# FPGA.net
KiCad netlist of a schematic drawn in Altium Designer
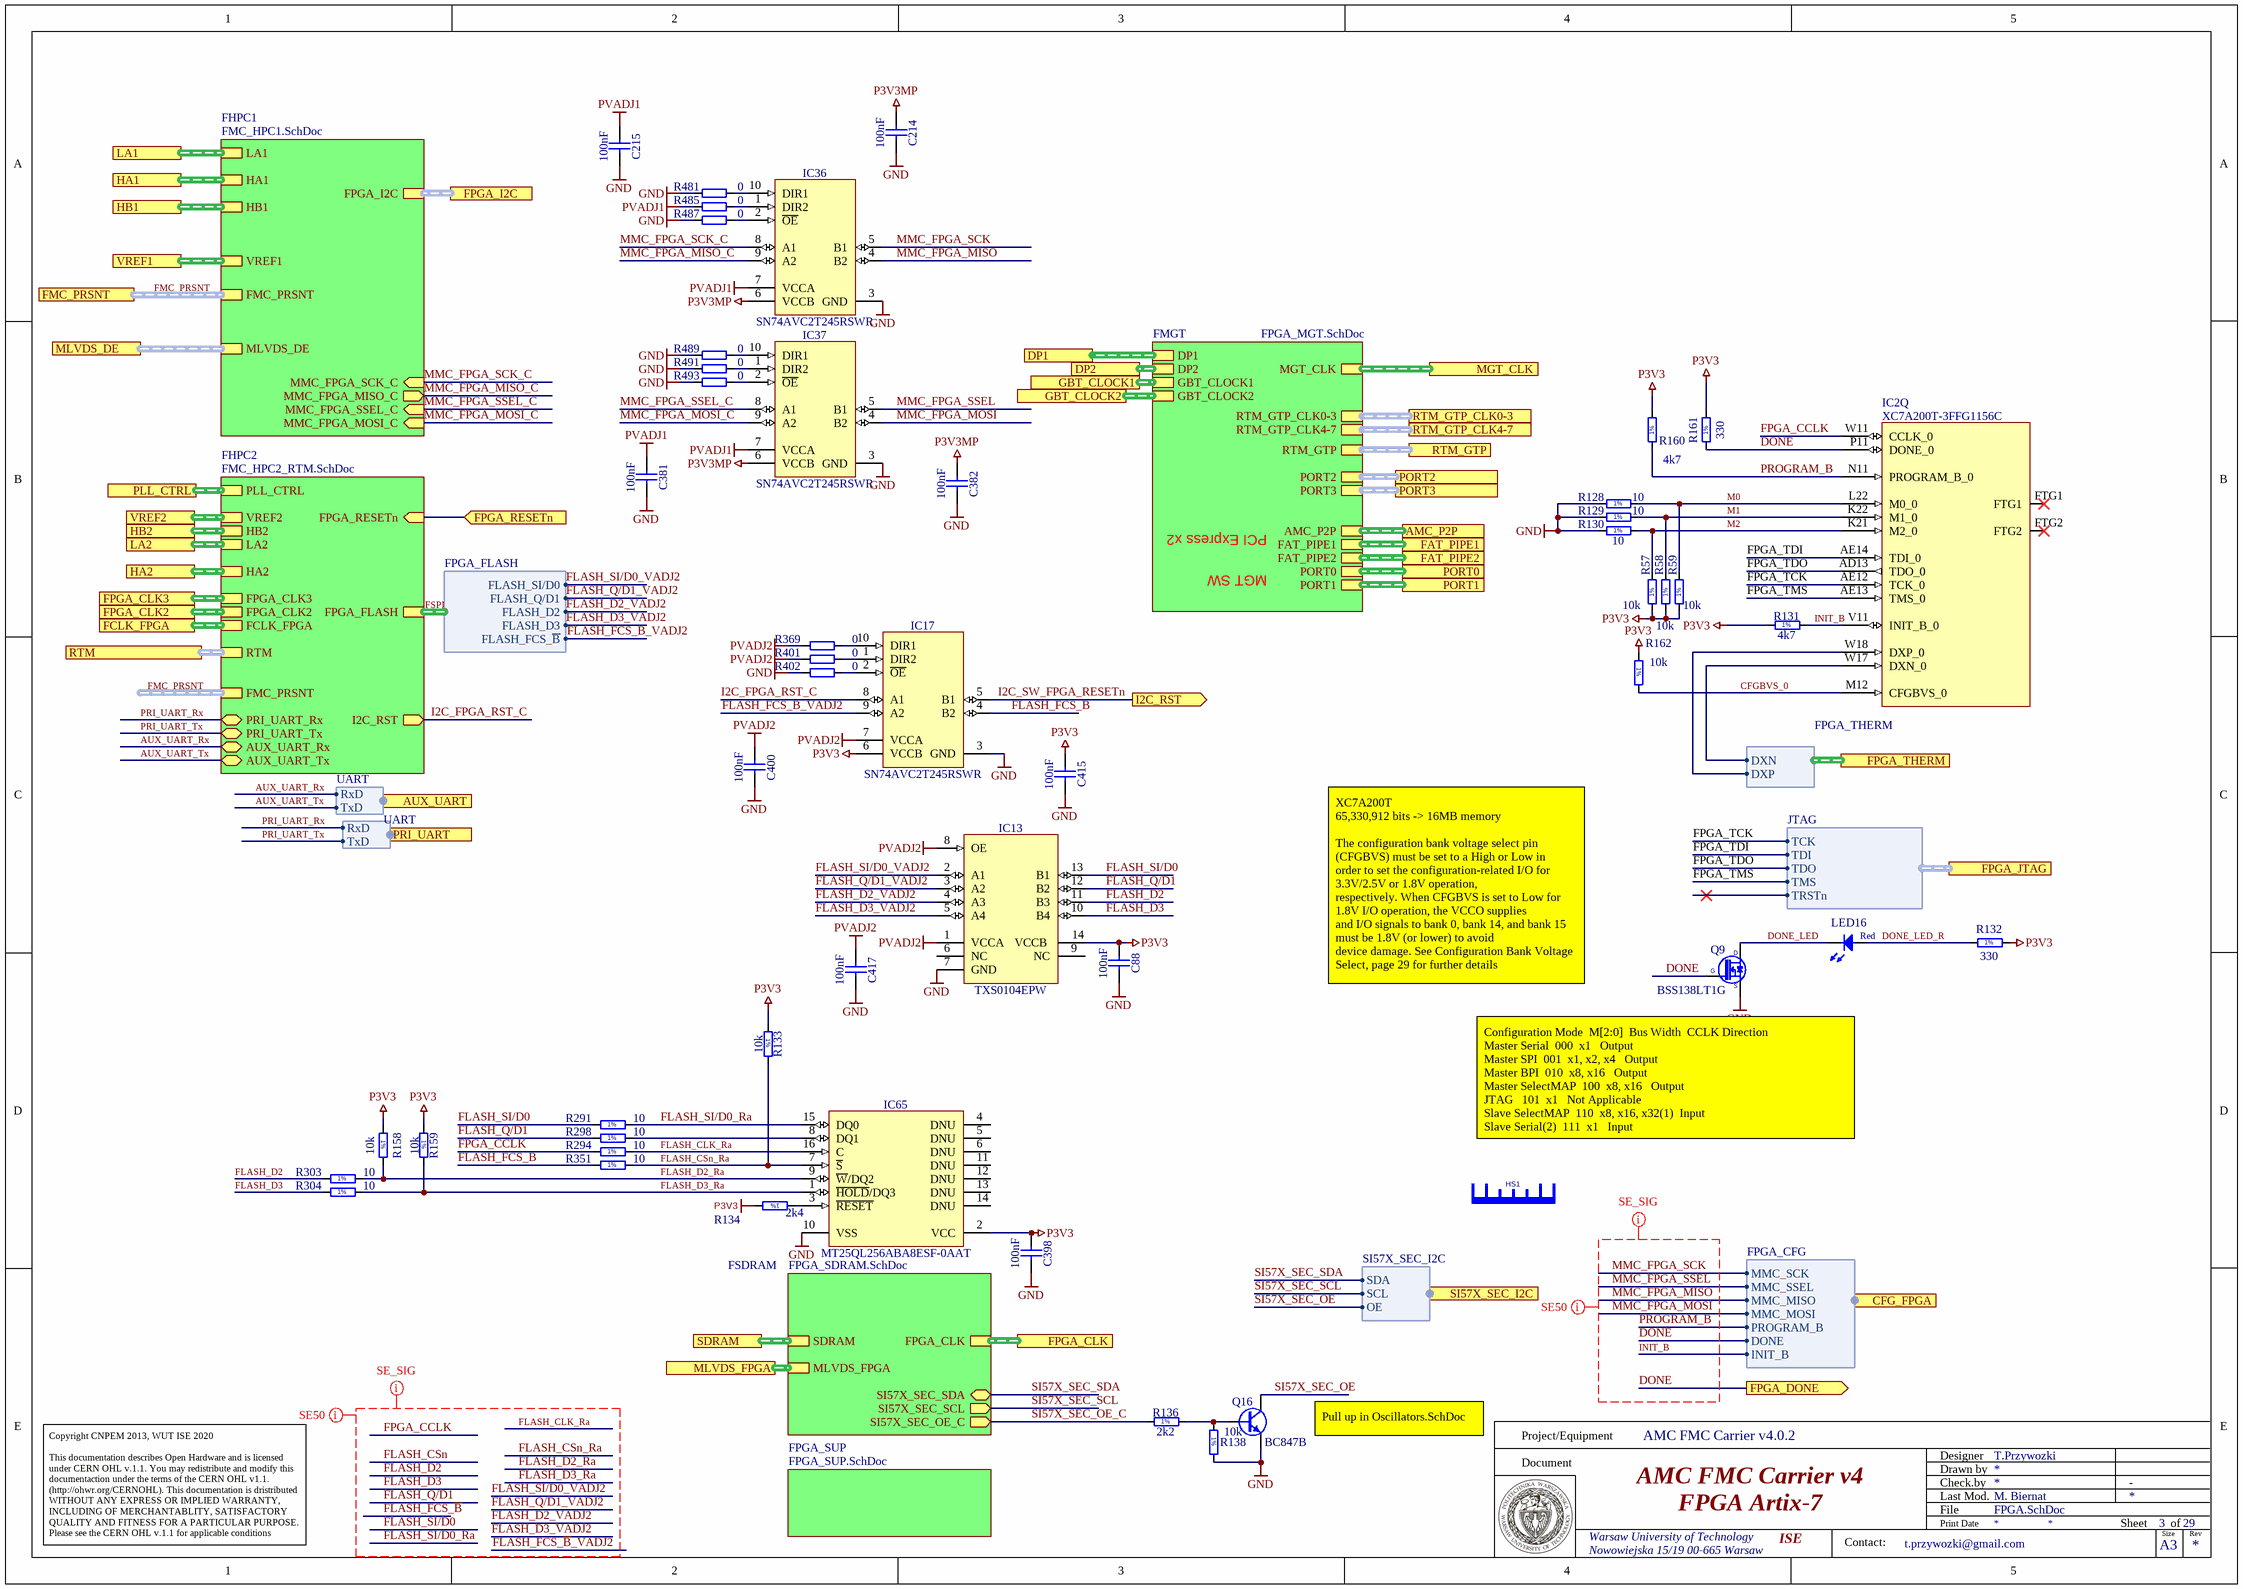
[diagram p0: FPGA.SchDoc]

(export (version "E")
  (design (tool "Eeschema 10.0.6"))
  (components
    (comp (ref "C88")
      (value "100nF")
      (footprint "CAPC0603X33N")
      (description "Non-polarised capacitor")
      (fields
        (field (name "PART NUMBER") "CC0201_100NF_6.3V_10%_X5R")
        (field (name "VOLTAGE") "6.3V")
        (field (name "AUTHOR") "CERN DEM JLC")
      )
      (libsource (lib "Capacitors") (part "Capacitor - non polarized"))
    )
    (comp (ref "C214")
      (value "100nF")
      (footprint "CAPC0603X33N")
      (description "Non-polarised capacitor")
      (fields
        (field (name "PART NUMBER") "CC0201_100NF_6.3V_10%_X5R")
        (field (name "VOLTAGE") "6.3V")
        (field (name "AUTHOR") "CERN DEM JLC")
      )
      (libsource (lib "Capacitors") (part "Capacitor - non polarized"))
    )
    (comp (ref "C215")
      (value "100nF")
      (footprint "CAPC0603X33N")
      (description "Non-polarised capacitor")
      (fields
        (field (name "PART NUMBER") "CC0201_100NF_6.3V_10%_X5R")
        (field (name "VOLTAGE") "6.3V")
        (field (name "AUTHOR") "CERN DEM JLC")
      )
      (libsource (lib "Capacitors") (part "Capacitor - non polarized"))
    )
    (comp (ref "C381")
      (value "100nF")
      (footprint "CAPC0603X33N")
      (description "Non-polarised capacitor")
      (fields
        (field (name "PART NUMBER") "CC0201_100NF_6.3V_10%_X5R")
        (field (name "VOLTAGE") "6.3V")
        (field (name "AUTHOR") "CERN DEM JLC")
      )
      (libsource (lib "Capacitors") (part "Capacitor - non polarized"))
    )
    (comp (ref "C382")
      (value "100nF")
      (footprint "CAPC0603X33N")
      (description "Non-polarised capacitor")
      (fields
        (field (name "PART NUMBER") "CC0201_100NF_6.3V_10%_X5R")
        (field (name "VOLTAGE") "6.3V")
        (field (name "AUTHOR") "CERN DEM JLC")
      )
      (libsource (lib "Capacitors") (part "Capacitor - non polarized"))
    )
    (comp (ref "C398")
      (value "100nF")
      (footprint "CAPC0603X33N")
      (description "Non-polarised capacitor")
      (fields
        (field (name "PART NUMBER") "CC0201_100NF_6.3V_10%_X5R")
        (field (name "VOLTAGE") "6.3V")
        (field (name "AUTHOR") "CERN DEM JLC")
      )
      (libsource (lib "Capacitors") (part "Capacitor - non polarized"))
    )
    (comp (ref "C400")
      (value "100nF")
      (footprint "CAPC0603X33N")
      (description "Non-polarised capacitor")
      (fields
        (field (name "PART NUMBER") "CC0201_100NF_6.3V_10%_X5R")
        (field (name "VOLTAGE") "6.3V")
        (field (name "AUTHOR") "CERN DEM JLC")
      )
      (libsource (lib "Capacitors") (part "Capacitor - non polarized"))
    )
    (comp (ref "C415")
      (value "100nF")
      (footprint "CAPC0603X33N")
      (description "Non-polarised capacitor")
      (fields
        (field (name "PART NUMBER") "CC0201_100NF_6.3V_10%_X5R")
        (field (name "VOLTAGE") "6.3V")
        (field (name "AUTHOR") "CERN DEM JLC")
      )
      (libsource (lib "Capacitors") (part "Capacitor - non polarized"))
    )
    (comp (ref "C417")
      (value "100nF")
      (footprint "CAPC0603X33N")
      (description "Non-polarised capacitor")
      (fields
        (field (name "PART NUMBER") "CC0201_100NF_6.3V_10%_X5R")
        (field (name "VOLTAGE") "6.3V")
        (field (name "AUTHOR") "CERN DEM JLC")
      )
      (libsource (lib "Capacitors") (part "Capacitor - non polarized"))
    )
    (comp (ref "HS1")
      (value "Heat Sink No Pad")
      (footprint "HSINK_ATS_ATS-50350B-C1-R0")
      (description "Heat Sink Without Pad")
      (fields
        (field (name "PART NUMBER") "HSINK_ATS_ATS-50350B-C1-R0")
        (field (name "MANUFACTURER") "ADVENCED THERMAL SOLUTION (ATS)")
        (field (name "AUTHOR") "CERN DEM JLC")
      )
      (libsource (lib "Eletro-mechanical") (part "Heat Sink No Pad"))
    )
    (comp (ref "IC2")
      (value "XC7A200T-3FFG1156C")
      (footprint "BGA1156C100P34X34_3500X3500X335")
      (description "Artix-6 FPGA, 16 GTPs, 600 User I/Os, 1156-Pin BGA, Speed Grade 2, Commercial Grade, Pb-Free")
      (fields
        (field (name "MANUFACTURER") "XILINX")
        (field (name "MANUFACTURER PART NUMBER") "XC7A350T-2FFG1156C")
        (field (name "AUTHOR") "CERN DEM JLC")
      )
      (libsource (lib "AMC_FMC_Carrier") (part "XC7A200T-3FFG1156C"))
    )
    (comp (ref "IC13")
      (value "TXS0104EPW")
      (footprint "SOP65P640X120-14N")
      (description "4-Bit Bidirectional Voltage-Level Translator For Open-Drain And Push-Pull Applications")
      (fields (field (name "MANUFACTURER") "TEXAS INSTRUMENTS") (field (name "AUTHOR") "CERN DEM MR"))
      (libsource (lib "ICs And Semiconductors") (part "TXS0104EPW"))
    )
    (comp (ref "IC17")
      (value "SN74AVC2T245RSWR")
      (footprint "QFN40P140X180X55-10N")
      (description "Dual-Bit Dual-Supply Bus Transceiver With Configurable Voltage Translation and 3-State Outputs")
      (fields (field (name "MANUFACTURER") "TEXAS INSTRUMENTS") (field (name "AUTHOR") "CERN DEM JLC"))
      (libsource (lib "ICs And Semiconductors") (part "742T245"))
    )
    (comp (ref "IC36")
      (value "SN74AVC2T245RSWR")
      (footprint "QFN40P140X180X55-10N")
      (description "Dual-Bit Dual-Supply Bus Transceiver With Configurable Voltage Translation and 3-State Outputs")
      (fields (field (name "MANUFACTURER") "TEXAS INSTRUMENTS") (field (name "AUTHOR") "CERN DEM JLC"))
      (libsource (lib "ICs And Semiconductors") (part "742T245"))
    )
    (comp (ref "IC37")
      (value "SN74AVC2T245RSWR")
      (footprint "QFN40P140X180X55-10N")
      (description "Dual-Bit Dual-Supply Bus Transceiver With Configurable Voltage Translation and 3-State Outputs")
      (fields (field (name "MANUFACTURER") "TEXAS INSTRUMENTS") (field (name "AUTHOR") "CERN DEM JLC"))
      (libsource (lib "ICs And Semiconductors") (part "742T245"))
    )
    (comp (ref "IC65")
      (value "MT25QL256ABA8ESF-0AAT")
      (footprint "SOIC127P1030X265-16N")
      (description "256Mbit (32MB), 2.7V-3.6V, Multiple I/O Serial NOR Flash Memory,with Reset# & Hold#")
      (fields (field (name "MANUFACTURER") "MICRON TECHNOLOGY") (field (name "AUTHOR") "CERN DEM JLC"))
      (libsource (lib "ICs And Semiconductors") (part "MT25QL256ABA8ESF"))
    )
    (comp (ref "LED16")
      (value "Red")
      (footprint "LED_KINGBRIGHT_KPH-1608SURCK")
      (description "LED Red 1C 2A")
      (fields
        (field (name "PART NUMBER") "LED_KINGBRIGHT_KPH-1608SURCK")
        (field (name "MANUFACTURER") "KINGBRIGHT")
        (field (name "AUTHOR") "CERN DEM JLC")
      )
      (libsource (lib "ICs And Semiconductors") (part "LED Red 1C 2A"))
    )
    (comp (ref "Q9")
      (value "BSS138LT1G")
      (footprint "SOT95P240X110-3N")
      (description "N-CHANNEL MOSFET WITH DIODE")
      (fields (field (name "MANUFACTURER") "ON SEMICONDUCTOR") (field (name "AUTHOR") "CERN DEM JLC"))
      (libsource (lib "ICs And Semiconductors") (part "N-MOSFET-D 1G 2S 3D"))
    )
    (comp (ref "Q16")
      (value "BC847B")
      (footprint "SOT95P230X110-3N")
      (description "NPN Transistor")
      (fields (field (name "MANUFACTURER") "NXP SEMICONDUCTORS") (field (name "AUTHOR") "CERN DEM JLC"))
      (libsource (lib "ICs And Semiconductors") (part "NPN B1 E2 C3"))
    )
    (comp (ref "R57")
      (value "10k")
      (footprint "RESC1005X40N")
      (description "Resistor - 1%")
      (fields
        (field (name "PART NUMBER") "R0402_10K_1%_0.0625W_100PPM")
        (field (name "POWER") "0.0625W")
        (field (name "AUTHOR") "CERN DEM JLC")
      )
      (libsource (lib "Resistors") (part "Resistor - 1%"))
    )
    (comp (ref "R58")
      (value "10k")
      (footprint "RESC1005X40N")
      (description "Resistor - 1%")
      (fields
        (field (name "PART NUMBER") "R0402_10K_1%_0.0625W_100PPM")
        (field (name "POWER") "0.0625W")
        (field (name "AUTHOR") "CERN DEM JLC")
      )
      (libsource (lib "Resistors") (part "Resistor - 1%"))
    )
    (comp (ref "R59")
      (value "10k")
      (footprint "RESC1005X40N")
      (description "Resistor - 1%")
      (fields
        (field (name "PART NUMBER") "R0402_10K_1%_0.0625W_100PPM")
        (field (name "POWER") "0.0625W")
        (field (name "AUTHOR") "CERN DEM JLC")
      )
      (libsource (lib "Resistors") (part "Resistor - 1%"))
    )
    (comp (ref "R128")
      (value "10")
      (footprint "RESC1005X40N")
      (description "Resistor - 1%")
      (fields
        (field (name "PART NUMBER") "R0402_10R_1%_0.0625W_200PPM")
        (field (name "POWER") "0.0625W")
        (field (name "AUTHOR") "CERN DEM JLC")
      )
      (libsource (lib "Resistors") (part "Resistor - 1%"))
    )
    (comp (ref "R129")
      (value "10")
      (footprint "RESC1005X40N")
      (description "Resistor - 1%")
      (fields
        (field (name "PART NUMBER") "R0402_10R_1%_0.0625W_200PPM")
        (field (name "POWER") "0.0625W")
        (field (name "AUTHOR") "CERN DEM JLC")
      )
      (libsource (lib "Resistors") (part "Resistor - 1%"))
    )
    (comp (ref "R130")
      (value "10")
      (footprint "RESC1005X40N")
      (description "Resistor - 1%")
      (fields
        (field (name "PART NUMBER") "R0402_10R_1%_0.0625W_200PPM")
        (field (name "POWER") "0.0625W")
        (field (name "AUTHOR") "CERN DEM JLC")
      )
      (libsource (lib "Resistors") (part "Resistor - 1%"))
    )
    (comp (ref "R131")
      (value "4k7")
      (footprint "RESC1005X40N")
      (description "Resistor - 1%")
      (fields
        (field (name "PART NUMBER") "R0402_4K7_1%_0.0625W_100PPM")
        (field (name "POWER") "0.0625W")
        (field (name "AUTHOR") "CERN DEM JLC")
      )
      (libsource (lib "Resistors") (part "Resistor - 1%"))
    )
    (comp (ref "R132")
      (value "330")
      (footprint "RESC1005X40N")
      (description "Resistor - 1%")
      (fields
        (field (name "PART NUMBER") "R0402_330R_1%_0.0625W_100PPM")
        (field (name "POWER") "0.0625W")
        (field (name "AUTHOR") "CERN DEM JLC")
      )
      (libsource (lib "Resistors") (part "Resistor - 1%"))
    )
    (comp (ref "R133")
      (value "10k")
      (footprint "RESC1005X40N")
      (description "Resistor - 1%")
      (fields
        (field (name "PART NUMBER") "R0402_10K_1%_0.0625W_100PPM")
        (field (name "POWER") "0.0625W")
        (field (name "AUTHOR") "CERN DEM JLC")
      )
      (libsource (lib "Resistors") (part "Resistor - 1%"))
    )
    (comp (ref "R134")
      (value "2k4")
      (footprint "RESC1005X40N")
      (description "Resistor - 1%")
      (fields
        (field (name "MANUFACTURER PART NUMBER") "R0402_2K4_1%_0.0625W_100PPM")
        (field (name "MANUFACTURER") "GENERIC")
        (field (name "AUTHOR") "CERN DEM JLC")
      )
      (libsource (lib "Resistors") (part "Resistor - 1%"))
    )
    (comp (ref "R136")
      (value "2k2")
      (footprint "RESC1005X40N")
      (description "Resistor - 1%")
      (fields
        (field (name "PART NUMBER") "R0402_2K2_1%_0.0625W_100PPM")
        (field (name "POWER") "0.0625W")
        (field (name "AUTHOR") "CERN DEM JLC")
      )
      (libsource (lib "Resistors") (part "Resistor - 1%"))
    )
    (comp (ref "R138")
      (value "10k")
      (footprint "RESC1005X40N")
      (description "Resistor - 1%")
      (fields
        (field (name "PART NUMBER") "R0402_10K_1%_0.0625W_100PPM")
        (field (name "POWER") "0.0625W")
        (field (name "AUTHOR") "CERN DEM JLC")
      )
      (libsource (lib "Resistors") (part "Resistor - 1%"))
    )
    (comp (ref "R158")
      (value "10k")
      (footprint "RESC1005X40N")
      (description "Resistor - 1%")
      (fields
        (field (name "PART NUMBER") "R0402_10K_1%_0.0625W_100PPM")
        (field (name "POWER") "0.0625W")
        (field (name "AUTHOR") "CERN DEM JLC")
      )
      (libsource (lib "Resistors") (part "Resistor - 1%"))
    )
    (comp (ref "R159")
      (value "10k")
      (footprint "RESC1005X40N")
      (description "Resistor - 1%")
      (fields
        (field (name "PART NUMBER") "R0402_10K_1%_0.0625W_100PPM")
        (field (name "POWER") "0.0625W")
        (field (name "AUTHOR") "CERN DEM JLC")
      )
      (libsource (lib "Resistors") (part "Resistor - 1%"))
    )
    (comp (ref "R160")
      (value "4k7")
      (footprint "RESC1005X40N")
      (description "Resistor - 1%")
      (fields
        (field (name "PART NUMBER") "R0402_4K7_1%_0.0625W_100PPM")
        (field (name "POWER") "0.0625W")
        (field (name "AUTHOR") "CERN DEM JLC")
      )
      (libsource (lib "Resistors") (part "Resistor - 1%"))
    )
    (comp (ref "R161")
      (value "330")
      (footprint "RESC1005X40N")
      (description "Resistor - 1%")
      (fields
        (field (name "PART NUMBER") "R0402_330R_1%_0.0625W_100PPM")
        (field (name "POWER") "0.0625W")
        (field (name "AUTHOR") "CERN DEM JLC")
      )
      (libsource (lib "Resistors") (part "Resistor - 1%"))
    )
    (comp (ref "R162")
      (value "10k")
      (footprint "RESC1005X40N")
      (description "Resistor - 1%")
      (fields
        (field (name "PART NUMBER") "R0402_10K_1%_0.0625W_100PPM")
        (field (name "POWER") "0.0625W")
        (field (name "AUTHOR") "CERN DEM JLC")
      )
      (libsource (lib "Resistors") (part "Resistor - 1%"))
    )
    (comp (ref "R291")
      (value "10")
      (footprint "RESC1005X40N")
      (description "Resistor - 1%")
      (fields
        (field (name "PART NUMBER") "R0402_10R_1%_0.0625W_200PPM")
        (field (name "POWER") "0.0625W")
        (field (name "AUTHOR") "CERN DEM JLC")
      )
      (libsource (lib "Resistors") (part "Resistor - 1%"))
    )
    (comp (ref "R294")
      (value "10")
      (footprint "RESC1005X40N")
      (description "Resistor - 1%")
      (fields
        (field (name "PART NUMBER") "R0402_10R_1%_0.0625W_200PPM")
        (field (name "POWER") "0.0625W")
        (field (name "AUTHOR") "CERN DEM JLC")
      )
      (libsource (lib "Resistors") (part "Resistor - 1%"))
    )
    (comp (ref "R298")
      (value "10")
      (footprint "RESC1005X40N")
      (description "Resistor - 1%")
      (fields
        (field (name "PART NUMBER") "R0402_10R_1%_0.0625W_200PPM")
        (field (name "POWER") "0.0625W")
        (field (name "AUTHOR") "CERN DEM JLC")
      )
      (libsource (lib "Resistors") (part "Resistor - 1%"))
    )
    (comp (ref "R303")
      (value "10")
      (footprint "RESC1005X40N")
      (description "Resistor - 1%")
      (fields
        (field (name "PART NUMBER") "R0402_10R_1%_0.0625W_200PPM")
        (field (name "POWER") "0.0625W")
        (field (name "AUTHOR") "CERN DEM JLC")
      )
      (libsource (lib "Resistors") (part "Resistor - 1%"))
    )
    (comp (ref "R304")
      (value "10")
      (footprint "RESC1005X40N")
      (description "Resistor - 1%")
      (fields
        (field (name "PART NUMBER") "R0402_10R_1%_0.0625W_200PPM")
        (field (name "POWER") "0.0625W")
        (field (name "AUTHOR") "CERN DEM JLC")
      )
      (libsource (lib "Resistors") (part "Resistor - 1%"))
    )
    (comp (ref "R351")
      (value "10")
      (footprint "RESC1005X40N")
      (description "Resistor - 1%")
      (fields
        (field (name "PART NUMBER") "R0402_10R_1%_0.0625W_200PPM")
        (field (name "POWER") "0.0625W")
        (field (name "AUTHOR") "CERN DEM JLC")
      )
      (libsource (lib "Resistors") (part "Resistor - 1%"))
    )
    (comp (ref "R369")
      (value "0")
      (footprint "RESC0603X28N")
      (description "Resistor")
      (fields
        (field (name "PART NUMBER") "R0201_0R_JUMPER")
        (field (name "MANUFACTURER") "GENERIC")
        (field (name "AUTHOR") "CERN DEM JLC")
      )
      (libsource (lib "Resistors") (part "Resistor"))
    )
    (comp (ref "R401")
      (value "0")
      (footprint "RESC0603X28N")
      (description "Resistor")
      (fields
        (field (name "PART NUMBER") "R0201_0R_JUMPER")
        (field (name "MANUFACTURER") "GENERIC")
        (field (name "AUTHOR") "CERN DEM JLC")
      )
      (libsource (lib "Resistors") (part "Resistor"))
    )
    (comp (ref "R402")
      (value "0")
      (footprint "RESC0603X28N")
      (description "Resistor")
      (fields
        (field (name "PART NUMBER") "R0201_0R_JUMPER")
        (field (name "MANUFACTURER") "GENERIC")
        (field (name "AUTHOR") "CERN DEM JLC")
      )
      (libsource (lib "Resistors") (part "Resistor"))
    )
    (comp (ref "R481")
      (value "0")
      (footprint "RESC1005X40N")
      (description "Resistor")
      (fields
        (field (name "MANUFACTURER PART NUMBER") "R0402_0R_JUMPER")
        (field (name "MANUFACTURER") "GENERIC")
        (field (name "AUTHOR") "CERN DEM JLC")
      )
      (libsource (lib "Resistors") (part "Resistor"))
    )
    (comp (ref "R485")
      (value "0")
      (footprint "RESC1005X40N")
      (description "Resistor")
      (fields
        (field (name "MANUFACTURER PART NUMBER") "R0402_0R_JUMPER")
        (field (name "MANUFACTURER") "GENERIC")
        (field (name "AUTHOR") "CERN DEM JLC")
      )
      (libsource (lib "Resistors") (part "Resistor"))
    )
    (comp (ref "R487")
      (value "0")
      (footprint "RESC1005X40N")
      (description "Resistor")
      (fields
        (field (name "MANUFACTURER PART NUMBER") "R0402_0R_JUMPER")
        (field (name "MANUFACTURER") "GENERIC")
        (field (name "AUTHOR") "CERN DEM JLC")
      )
      (libsource (lib "Resistors") (part "Resistor"))
    )
    (comp (ref "R489")
      (value "0")
      (footprint "RESC1005X40N")
      (description "Resistor")
      (fields
        (field (name "MANUFACTURER PART NUMBER") "R0402_0R_JUMPER")
        (field (name "MANUFACTURER") "GENERIC")
        (field (name "AUTHOR") "CERN DEM JLC")
      )
      (libsource (lib "Resistors") (part "Resistor"))
    )
    (comp (ref "R491")
      (value "0")
      (footprint "RESC1005X40N")
      (description "Resistor")
      (fields
        (field (name "MANUFACTURER PART NUMBER") "R0402_0R_JUMPER")
        (field (name "MANUFACTURER") "GENERIC")
        (field (name "AUTHOR") "CERN DEM JLC")
      )
      (libsource (lib "Resistors") (part "Resistor"))
    )
    (comp (ref "R493")
      (value "0")
      (footprint "RESC1005X40N")
      (description "Resistor")
      (fields
        (field (name "MANUFACTURER PART NUMBER") "R0402_0R_JUMPER")
        (field (name "MANUFACTURER") "GENERIC")
        (field (name "AUTHOR") "CERN DEM JLC")
      )
      (libsource (lib "Resistors") (part "Resistor"))
    )
  )
  (nets
    (net (code "32") (name "/CFGBVS_0") (class "Default")
      (node (ref "IC2") (pin "M12") (pinfunction "CFGBVS_0_M12") (pintype "input"))
      (node (ref "R162") (pin "2") (pinfunction "2_2") (pintype "passive"))
    )
    (net (code "33") (name "/DONE") (class "Default")
      (node (ref "IC2") (pin "P11") (pinfunction "DONE_0_P11") (pintype "bidirectional"))
      (node (ref "Q9") (pin "1") (pinfunction "G_1") (pintype "passive"))
      (node (ref "R161") (pin "1") (pinfunction "1_1") (pintype "passive"))
    )
    (net (code "34") (name "/DONE_LED") (class "Default")
      (node (ref "LED16") (pin "1") (pinfunction "C_1") (pintype "passive"))
      (node (ref "Q9") (pin "3") (pinfunction "D_3") (pintype "passive"))
    )
    (net (code "35") (name "/DONE_LED_R") (class "Default")
      (node (ref "LED16") (pin "2") (pinfunction "A_2") (pintype "passive"))
      (node (ref "R132") (pin "1") (pinfunction "1_1") (pintype "passive"))
    )
    (net (code "38") (name "/DXN") (class "Default")
      (node (ref "IC2") (pin "W17") (pinfunction "DXN_0_W17") (pintype "input"))
    )
    (net (code "39") (name "/DXP") (class "Default")
      (node (ref "IC2") (pin "W18") (pinfunction "DXP_0_W18") (pintype "input"))
    )
    (net (code "45") (name "/FLASH_CLK_Ra") (class "Default")
      (node (ref "IC65") (pin "16") (pinfunction "C_16") (pintype "input"))
      (node (ref "R294") (pin "2") (pinfunction "2_2") (pintype "passive"))
    )
    (net (code "47") (name "/FLASH_CSn_Ra") (class "Default")
      (node (ref "IC65") (pin "7") (pinfunction "~{S}_7") (pintype "input"))
      (node (ref "R133") (pin "2") (pinfunction "2_2") (pintype "passive"))
      (node (ref "R351") (pin "2") (pinfunction "2_2") (pintype "passive"))
    )
    (net (code "48") (name "/FLASH_D2") (class "Default")
      (node (ref "IC13") (pin "11") (pinfunction "B3_11") (pintype "bidirectional"))
      (node (ref "R303") (pin "1") (pinfunction "1_1") (pintype "passive"))
    )
    (net (code "49") (name "/FLASH_D2_Ra") (class "Default")
      (node (ref "IC65") (pin "9") (pinfunction "~{W}/DQ2_9") (pintype "bidirectional"))
      (node (ref "R158") (pin "2") (pinfunction "2_2") (pintype "passive"))
      (node (ref "R303") (pin "2") (pinfunction "2_2") (pintype "passive"))
    )
    (net (code "50") (name "/FLASH_D2_VADJ2") (class "Default")
      (node (ref "IC13") (pin "4") (pinfunction "A3_4") (pintype "bidirectional"))
    )
    (net (code "51") (name "/FLASH_D3") (class "Default")
      (node (ref "IC13") (pin "10") (pinfunction "B4_10") (pintype "bidirectional"))
      (node (ref "R304") (pin "1") (pinfunction "1_1") (pintype "passive"))
    )
    (net (code "52") (name "/FLASH_D3_Ra") (class "Default")
      (node (ref "IC65") (pin "1") (pinfunction "~{HOLD}/DQ3_1") (pintype "bidirectional"))
      (node (ref "R159") (pin "2") (pinfunction "2_2") (pintype "passive"))
      (node (ref "R304") (pin "2") (pinfunction "2_2") (pintype "passive"))
    )
    (net (code "53") (name "/FLASH_D3_VADJ2") (class "Default")
      (node (ref "IC13") (pin "5") (pinfunction "A4_5") (pintype "bidirectional"))
    )
    (net (code "54") (name "/FLASH_FCS_~{B}") (class "Default")
      (node (ref "IC17") (pin "4") (pinfunction "B2_4") (pintype "bidirectional"))
      (node (ref "R351") (pin "1") (pinfunction "1_1") (pintype "passive"))
    )
    (net (code "55") (name "/FLASH_FCS_~{B}_VADJ2") (class "Default")
      (node (ref "IC17") (pin "9") (pinfunction "A2_9") (pintype "bidirectional"))
    )
    (net (code "56") (name "/FLASH_Q{slash}D1") (class "Default")
      (node (ref "IC13") (pin "12") (pinfunction "B2_12") (pintype "bidirectional"))
      (node (ref "R298") (pin "2") (pinfunction "2_2") (pintype "passive"))
    )
    (net (code "57") (name "/FLASH_Q{slash}D1_VADJ2") (class "Default")
      (node (ref "IC13") (pin "3") (pinfunction "A2_3") (pintype "bidirectional"))
    )
    (net (code "58") (name "/FLASH_SI{slash}D0") (class "Default")
      (node (ref "IC13") (pin "13") (pinfunction "B1_13") (pintype "bidirectional"))
      (node (ref "R291") (pin "1") (pinfunction "1_1") (pintype "passive"))
    )
    (net (code "59") (name "/FLASH_SI{slash}D0_Ra") (class "Default")
      (node (ref "IC65") (pin "15") (pinfunction "DQ0_15") (pintype "bidirectional"))
      (node (ref "R291") (pin "2") (pinfunction "2_2") (pintype "passive"))
    )
    (net (code "60") (name "/FLASH_SI{slash}D0_VADJ2") (class "Default")
      (node (ref "IC13") (pin "2") (pinfunction "A1_2") (pintype "bidirectional"))
    )
    (net (code "61") (name "/FPGA_CCLK") (class "Default")
      (node (ref "IC2") (pin "W11") (pinfunction "CCLK_0_W11") (pintype "bidirectional"))
      (node (ref "R294") (pin "1") (pinfunction "1_1") (pintype "passive"))
    )
    (net (code "68") (name "/FPGA_TCK") (class "Default")
      (node (ref "IC2") (pin "AE12") (pinfunction "TCK_0_AE12") (pintype "input"))
    )
    (net (code "69") (name "/FPGA_TDI") (class "Default")
      (node (ref "IC2") (pin "AE14") (pinfunction "TDI_0_AE14") (pintype "input"))
    )
    (net (code "70") (name "/FPGA_TDO") (class "Default")
      (node (ref "IC2") (pin "AD13") (pinfunction "TDO_0_AD13") (pintype "output"))
    )
    (net (code "71") (name "/FPGA_TMS") (class "Default")
      (node (ref "IC2") (pin "AE13") (pinfunction "TMS_0_AE13") (pintype "input"))
    )
    (net (code "79") (name "/I2C_FPGA_RST_C") (class "Default")
      (node (ref "IC17") (pin "8") (pinfunction "A1_8") (pintype "bidirectional"))
    )
    (net (code "80") (name "/I2C_SW_FPGA_RESETn") (class "Default")
      (node (ref "IC17") (pin "5") (pinfunction "B1_5") (pintype "bidirectional"))
    )
    (net (code "81") (name "/INIT_B") (class "Default")
      (node (ref "IC2") (pin "V11") (pinfunction "INIT_B_0_V11") (pintype "bidirectional"))
      (node (ref "R131") (pin "2") (pinfunction "2_2") (pintype "passive"))
    )
    (net (code "84") (name "/M0") (class "Default")
      (node (ref "IC2") (pin "L22") (pinfunction "M0_0_L22") (pintype "input"))
      (node (ref "R128") (pin "2") (pinfunction "2_2") (pintype "passive"))
      (node (ref "R59") (pin "2") (pinfunction "2_2") (pintype "passive"))
    )
    (net (code "85") (name "/M1") (class "Default")
      (node (ref "IC2") (pin "K22") (pinfunction "M1_0_K22") (pintype "input"))
      (node (ref "R129") (pin "2") (pinfunction "2_2") (pintype "passive"))
      (node (ref "R58") (pin "2") (pinfunction "2_2") (pintype "passive"))
    )
    (net (code "86") (name "/M2") (class "Default")
      (node (ref "IC2") (pin "K21") (pinfunction "M2_0_K21") (pintype "input"))
      (node (ref "R130") (pin "2") (pinfunction "2_2") (pintype "passive"))
      (node (ref "R57") (pin "2") (pinfunction "2_2") (pintype "passive"))
    )
    (net (code "91") (name "/MMC_FPGA_MISO") (class "Default")
      (node (ref "IC36") (pin "4") (pinfunction "B2_4") (pintype "bidirectional"))
    )
    (net (code "92") (name "/MMC_FPGA_MISO_C") (class "Default")
      (node (ref "IC36") (pin "9") (pinfunction "A2_9") (pintype "bidirectional"))
    )
    (net (code "93") (name "/MMC_FPGA_MOSI") (class "Default")
      (node (ref "IC37") (pin "4") (pinfunction "B2_4") (pintype "bidirectional"))
    )
    (net (code "94") (name "/MMC_FPGA_MOSI_C") (class "Default")
      (node (ref "IC37") (pin "9") (pinfunction "A2_9") (pintype "bidirectional"))
    )
    (net (code "95") (name "/MMC_FPGA_SCK") (class "Default")
      (node (ref "IC36") (pin "5") (pinfunction "B1_5") (pintype "bidirectional"))
    )
    (net (code "96") (name "/MMC_FPGA_SCK_C") (class "Default")
      (node (ref "IC36") (pin "8") (pinfunction "A1_8") (pintype "bidirectional"))
    )
    (net (code "97") (name "/MMC_FPGA_SSEL") (class "Default")
      (node (ref "IC37") (pin "5") (pinfunction "B1_5") (pintype "bidirectional"))
    )
    (net (code "98") (name "/MMC_FPGA_SSEL_C") (class "Default")
      (node (ref "IC37") (pin "8") (pinfunction "A1_8") (pintype "bidirectional"))
    )
    (net (code "106") (name "/PROGRAM_B") (class "Default")
      (node (ref "IC2") (pin "N11") (pinfunction "PROGRAM_B_0_N11") (pintype "input"))
      (node (ref "R160") (pin "1") (pinfunction "1_1") (pintype "passive"))
    )
    (net (code "112") (name "/SI57X_SEC_OE") (class "Default")
      (node (ref "Q16") (pin "3") (pinfunction "C_3") (pintype "passive"))
    )
    (net (code "113") (name "/SI57X_SEC_OE_C") (class "Default")
      (node (ref "R136") (pin "1") (pinfunction "1_1") (pintype "passive"))
    )
    (net (code "125") (name "GND") (class "Default")
      (node (ref "C214") (pin "2") (pinfunction "2_2") (pintype "passive"))
      (node (ref "C215") (pin "2") (pinfunction "2_2") (pintype "passive"))
      (node (ref "C381") (pin "2") (pinfunction "2_2") (pintype "passive"))
      (node (ref "C382") (pin "2") (pinfunction "2_2") (pintype "passive"))
      (node (ref "C398") (pin "2") (pinfunction "2_2") (pintype "passive"))
      (node (ref "C400") (pin "2") (pinfunction "2_2") (pintype "passive"))
      (node (ref "C415") (pin "2") (pinfunction "2_2") (pintype "passive"))
      (node (ref "C417") (pin "2") (pinfunction "2_2") (pintype "passive"))
      (node (ref "C88") (pin "2") (pinfunction "2_2") (pintype "passive"))
      (node (ref "IC13") (pin "7") (pinfunction "GND_7") (pintype "power_in"))
      (node (ref "IC17") (pin "3") (pinfunction "GND_3") (pintype "power_in"))
      (node (ref "IC36") (pin "3") (pinfunction "GND_3") (pintype "power_in"))
      (node (ref "IC37") (pin "3") (pinfunction "GND_3") (pintype "power_in"))
      (node (ref "IC65") (pin "10") (pinfunction "VSS_10") (pintype "power_in"))
      (node (ref "Q16") (pin "2") (pinfunction "E_2") (pintype "passive"))
      (node (ref "Q9") (pin "2") (pinfunction "S_2") (pintype "passive"))
      (node (ref "R128") (pin "1") (pinfunction "1_1") (pintype "passive"))
      (node (ref "R129") (pin "1") (pinfunction "1_1") (pintype "passive"))
      (node (ref "R130") (pin "1") (pinfunction "1_1") (pintype "passive"))
      (node (ref "R138") (pin "2") (pinfunction "2_2") (pintype "passive"))
      (node (ref "R402") (pin "1") (pinfunction "1_1") (pintype "passive"))
      (node (ref "R481") (pin "1") (pinfunction "1_1") (pintype "passive"))
      (node (ref "R487") (pin "1") (pinfunction "1_1") (pintype "passive"))
      (node (ref "R489") (pin "1") (pinfunction "1_1") (pintype "passive"))
      (node (ref "R491") (pin "1") (pinfunction "1_1") (pintype "passive"))
      (node (ref "R493") (pin "1") (pinfunction "1_1") (pintype "passive"))
    )
    (net (code "126") (name "Net-(IC17-DIR1)") (class "Default")
      (node (ref "IC17") (pin "10") (pinfunction "DIR1_10") (pintype "input"))
      (node (ref "R369") (pin "2") (pinfunction "2_2") (pintype "passive"))
    )
    (net (code "127") (name "Net-(IC17-DIR2)") (class "Default")
      (node (ref "IC17") (pin "1") (pinfunction "DIR2_1") (pintype "input"))
      (node (ref "R401") (pin "2") (pinfunction "2_2") (pintype "passive"))
    )
    (net (code "128") (name "Net-(IC17-~{OE})") (class "Default")
      (node (ref "IC17") (pin "2") (pinfunction "~{OE}_2") (pintype "input"))
      (node (ref "R402") (pin "2") (pinfunction "2_2") (pintype "passive"))
    )
    (net (code "129") (name "Net-(IC36-DIR1)") (class "Default")
      (node (ref "IC36") (pin "10") (pinfunction "DIR1_10") (pintype "input"))
      (node (ref "R481") (pin "2") (pinfunction "2_2") (pintype "passive"))
    )
    (net (code "130") (name "Net-(IC36-DIR2)") (class "Default")
      (node (ref "IC36") (pin "1") (pinfunction "DIR2_1") (pintype "input"))
      (node (ref "R485") (pin "2") (pinfunction "2_2") (pintype "passive"))
    )
    (net (code "131") (name "Net-(IC36-~{OE})") (class "Default")
      (node (ref "IC36") (pin "2") (pinfunction "~{OE}_2") (pintype "input"))
      (node (ref "R487") (pin "2") (pinfunction "2_2") (pintype "passive"))
    )
    (net (code "132") (name "Net-(IC37-DIR1)") (class "Default")
      (node (ref "IC37") (pin "10") (pinfunction "DIR1_10") (pintype "input"))
      (node (ref "R489") (pin "2") (pinfunction "2_2") (pintype "passive"))
    )
    (net (code "133") (name "Net-(IC37-DIR2)") (class "Default")
      (node (ref "IC37") (pin "1") (pinfunction "DIR2_1") (pintype "input"))
      (node (ref "R491") (pin "2") (pinfunction "2_2") (pintype "passive"))
    )
    (net (code "134") (name "Net-(IC37-~{OE})") (class "Default")
      (node (ref "IC37") (pin "2") (pinfunction "~{OE}_2") (pintype "input"))
      (node (ref "R493") (pin "2") (pinfunction "2_2") (pintype "passive"))
    )
    (net (code "135") (name "Net-(IC65-DQ1)") (class "Default")
      (node (ref "IC65") (pin "8") (pinfunction "DQ1_8") (pintype "bidirectional"))
      (node (ref "R298") (pin "1") (pinfunction "1_1") (pintype "passive"))
    )
    (net (code "136") (name "Net-(IC65-~{RESET})") (class "Default")
      (node (ref "IC65") (pin "3") (pinfunction "~{RESET}_3") (pintype "input"))
      (node (ref "R134") (pin "1") (pinfunction "1_1") (pintype "passive"))
    )
    (net (code "137") (name "Net-(Q16-B)") (class "Default")
      (node (ref "Q16") (pin "1") (pinfunction "B_1") (pintype "passive"))
      (node (ref "R136") (pin "2") (pinfunction "2_2") (pintype "passive"))
      (node (ref "R138") (pin "1") (pinfunction "1_1") (pintype "passive"))
    )
    (net (code "138") (name "P3V3") (class "Default")
      (node (ref "C398") (pin "1") (pinfunction "1_1") (pintype "passive"))
      (node (ref "C415") (pin "1") (pinfunction "1_1") (pintype "passive"))
      (node (ref "C88") (pin "1") (pinfunction "1_1") (pintype "passive"))
      (node (ref "IC13") (pin "14") (pinfunction "VCCB_14") (pintype "power_in"))
      (node (ref "IC17") (pin "6") (pinfunction "VCCB_6") (pintype "power_in"))
      (node (ref "IC65") (pin "2") (pinfunction "VCC_2") (pintype "power_in"))
      (node (ref "R131") (pin "1") (pinfunction "1_1") (pintype "passive"))
      (node (ref "R132") (pin "2") (pinfunction "2_2") (pintype "passive"))
      (node (ref "R133") (pin "1") (pinfunction "1_1") (pintype "passive"))
      (node (ref "R134") (pin "2") (pinfunction "2_2") (pintype "passive"))
      (node (ref "R158") (pin "1") (pinfunction "1_1") (pintype "passive"))
      (node (ref "R159") (pin "1") (pinfunction "1_1") (pintype "passive"))
      (node (ref "R160") (pin "2") (pinfunction "2_2") (pintype "passive"))
      (node (ref "R161") (pin "2") (pinfunction "2_2") (pintype "passive"))
      (node (ref "R162") (pin "1") (pinfunction "1_1") (pintype "passive"))
      (node (ref "R57") (pin "1") (pinfunction "1_1") (pintype "passive"))
      (node (ref "R58") (pin "1") (pinfunction "1_1") (pintype "passive"))
      (node (ref "R59") (pin "1") (pinfunction "1_1") (pintype "passive"))
    )
    (net (code "139") (name "P3V3MP") (class "Default")
      (node (ref "C214") (pin "1") (pinfunction "1_1") (pintype "passive"))
      (node (ref "C382") (pin "1") (pinfunction "1_1") (pintype "passive"))
      (node (ref "IC36") (pin "6") (pinfunction "VCCB_6") (pintype "power_in"))
      (node (ref "IC37") (pin "6") (pinfunction "VCCB_6") (pintype "power_in"))
    )
    (net (code "140") (name "PVADJ1") (class "Default")
      (node (ref "C215") (pin "1") (pinfunction "1_1") (pintype "passive"))
      (node (ref "C381") (pin "1") (pinfunction "1_1") (pintype "passive"))
      (node (ref "IC36") (pin "7") (pinfunction "VCCA_7") (pintype "power_in"))
      (node (ref "IC37") (pin "7") (pinfunction "VCCA_7") (pintype "power_in"))
      (node (ref "R485") (pin "1") (pinfunction "1_1") (pintype "passive"))
    )
    (net (code "141") (name "PVADJ2") (class "Default")
      (node (ref "C400") (pin "1") (pinfunction "1_1") (pintype "passive"))
      (node (ref "C417") (pin "1") (pinfunction "1_1") (pintype "passive"))
      (node (ref "IC13") (pin "1") (pinfunction "VCCA_1") (pintype "power_in"))
      (node (ref "IC13") (pin "8") (pinfunction "OE_8") (pintype "input"))
      (node (ref "IC17") (pin "7") (pinfunction "VCCA_7") (pintype "power_in"))
      (node (ref "R369") (pin "1") (pinfunction "1_1") (pintype "passive"))
      (node (ref "R401") (pin "1") (pinfunction "1_1") (pintype "passive"))
    )
    (net (code "142") (name "unconnected-(IC2-PadFTG1)") (class "Default")
      (node (ref "IC2") (pin "FTG1") (pinfunction "FTG1_FTG1") (pintype "passive+no_connect"))
    )
    (net (code "143") (name "unconnected-(IC2-PadFTG2)") (class "Default")
      (node (ref "IC2") (pin "FTG2") (pinfunction "FTG2_FTG2") (pintype "passive+no_connect"))
    )
    (net (code "144") (name "unconnected-(IC13-NC-Pad6)") (class "Default")
      (node (ref "IC13") (pin "6") (pinfunction "NC_6") (pintype "passive"))
    )
    (net (code "145") (name "unconnected-(IC13-NC-Pad9)") (class "Default")
      (node (ref "IC13") (pin "9") (pinfunction "NC_9") (pintype "passive"))
    )
    (net (code "146") (name "unconnected-(IC65-DNU-Pad4)") (class "Default")
      (node (ref "IC65") (pin "4") (pinfunction "DNU_4") (pintype "passive"))
    )
    (net (code "147") (name "unconnected-(IC65-DNU-Pad5)") (class "Default")
      (node (ref "IC65") (pin "5") (pinfunction "DNU_5") (pintype "passive"))
    )
    (net (code "148") (name "unconnected-(IC65-DNU-Pad6)") (class "Default")
      (node (ref "IC65") (pin "6") (pinfunction "DNU_6") (pintype "passive"))
    )
    (net (code "149") (name "unconnected-(IC65-DNU-Pad11)") (class "Default")
      (node (ref "IC65") (pin "11") (pinfunction "DNU_11") (pintype "passive"))
    )
    (net (code "150") (name "unconnected-(IC65-DNU-Pad12)") (class "Default")
      (node (ref "IC65") (pin "12") (pinfunction "DNU_12") (pintype "passive"))
    )
    (net (code "151") (name "unconnected-(IC65-DNU-Pad13)") (class "Default")
      (node (ref "IC65") (pin "13") (pinfunction "DNU_13") (pintype "passive"))
    )
    (net (code "152") (name "unconnected-(IC65-DNU-Pad14)") (class "Default")
      (node (ref "IC65") (pin "14") (pinfunction "DNU_14") (pintype "passive"))
    )
  )
)
